# tlacitka.net
KiCad netlist of a schematic drawn in EAGLE
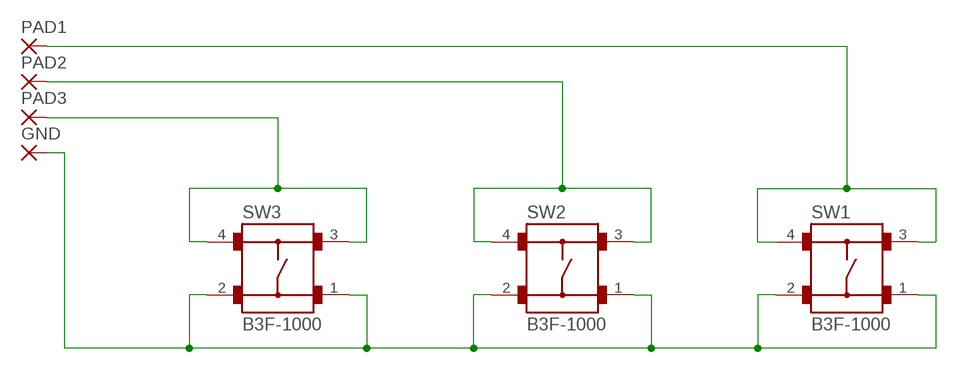
[diagram p0: schematic, sheet 1]

(export (version "E")
  (design (tool "Eeschema 10.0.6"))
  (components
    (comp (ref "GND")
      (value "SMD5")
      (footprint "eagle-import:SMD2,54-5,08")
      (libsource (lib "eagle-import") (part "SMD5"))
    )
    (comp (ref "PAD1")
      (value "SMD5")
      (footprint "eagle-import:SMD2,54-5,08")
      (libsource (lib "eagle-import") (part "SMD5"))
    )
    (comp (ref "PAD2")
      (value "SMD5")
      (footprint "eagle-import:SMD2,54-5,08")
      (libsource (lib "eagle-import") (part "SMD5"))
    )
    (comp (ref "PAD3")
      (value "SMD5")
      (footprint "eagle-import:SMD2,54-5,08")
      (libsource (lib "eagle-import") (part "SMD5"))
    )
    (comp (ref "SW1")
      (value "B3F-1000")
      (footprint "eagle-import:B3F-1000")
      (fields
        (field (name "DIGI_KEY_PART_NUMBER") "SW400-ND")
        (field (name "MANUFACTURER") "Omron Electronics Inc-EMC Div")
        (field (name "CREATED_BY") "PCBLayout.com")
      )
      (libsource (lib "eagle-import") (part "B3F-1000"))
    )
    (comp (ref "SW2")
      (value "B3F-1000")
      (footprint "eagle-import:B3F-1000")
      (fields
        (field (name "DIGI_KEY_PART_NUMBER") "SW400-ND")
        (field (name "MANUFACTURER") "Omron Electronics Inc-EMC Div")
        (field (name "CREATED_BY") "PCBLayout.com")
      )
      (libsource (lib "eagle-import") (part "B3F-1000"))
    )
    (comp (ref "SW3")
      (value "B3F-1000")
      (footprint "eagle-import:B3F-1000")
      (fields
        (field (name "DIGI_KEY_PART_NUMBER") "SW400-ND")
        (field (name "MANUFACTURER") "Omron Electronics Inc-EMC Div")
        (field (name "CREATED_BY") "PCBLayout.com")
      )
      (libsource (lib "eagle-import") (part "B3F-1000"))
    )
  )
  (nets
    (net (code "1") (name "Net-(GND-P)") (class "Default")
      (node (ref "GND") (pin "1") (pinfunction "P_1") (pintype "passive"))
      (node (ref "SW1") (pin "1") (pinfunction "1_1") (pintype "passive"))
      (node (ref "SW1") (pin "2") (pinfunction "2_2") (pintype "passive"))
      (node (ref "SW2") (pin "1") (pinfunction "1_1") (pintype "passive"))
      (node (ref "SW2") (pin "2") (pinfunction "2_2") (pintype "passive"))
      (node (ref "SW3") (pin "1") (pinfunction "1_1") (pintype "passive"))
      (node (ref "SW3") (pin "2") (pinfunction "2_2") (pintype "passive"))
    )
    (net (code "2") (name "Net-(PAD1-P)") (class "Default")
      (node (ref "PAD1") (pin "1") (pinfunction "P_1") (pintype "passive"))
      (node (ref "SW1") (pin "3") (pinfunction "3_3") (pintype "passive"))
      (node (ref "SW1") (pin "4") (pinfunction "4_4") (pintype "passive"))
    )
    (net (code "3") (name "Net-(PAD2-P)") (class "Default")
      (node (ref "PAD2") (pin "1") (pinfunction "P_1") (pintype "passive"))
      (node (ref "SW2") (pin "3") (pinfunction "3_3") (pintype "passive"))
      (node (ref "SW2") (pin "4") (pinfunction "4_4") (pintype "passive"))
    )
    (net (code "4") (name "Net-(PAD3-P)") (class "Default")
      (node (ref "PAD3") (pin "1") (pinfunction "P_1") (pintype "passive"))
      (node (ref "SW3") (pin "3") (pinfunction "3_3") (pintype "passive"))
      (node (ref "SW3") (pin "4") (pinfunction "4_4") (pintype "passive"))
    )
  )
)
